# MotorPower.net
KiCad netlist of a schematic drawn in Altium Designer
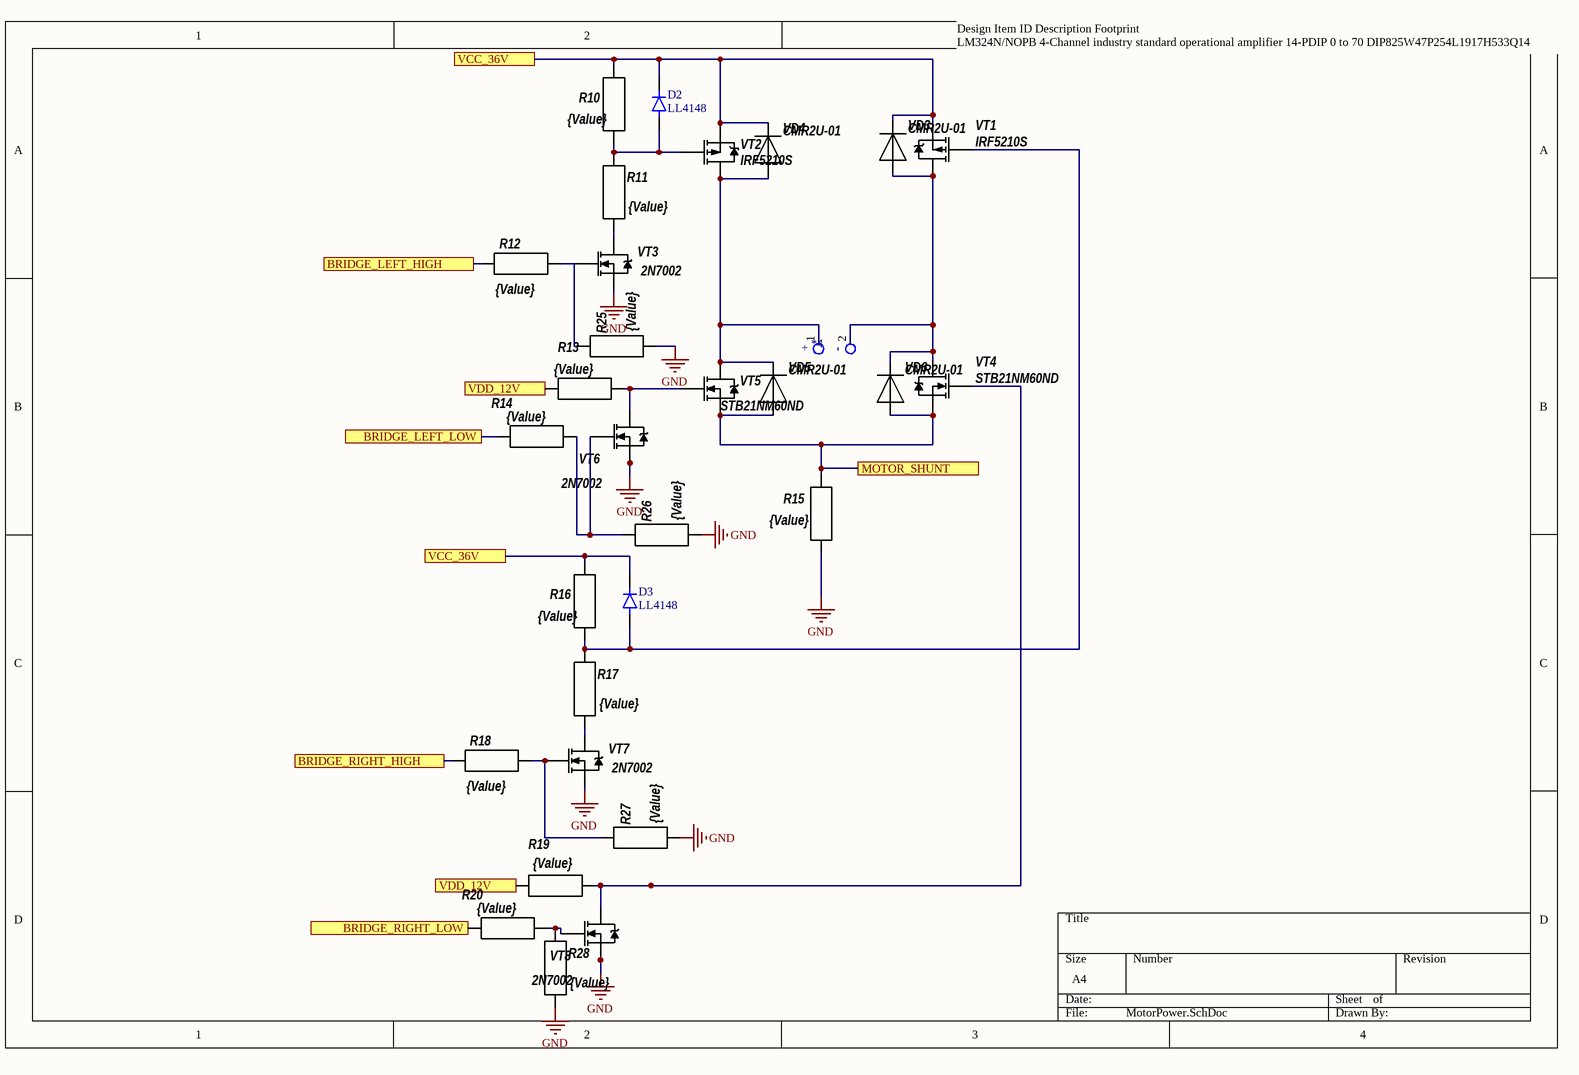
[diagram p0: MotorPower.SchDoc]

(export (version "E")
  (design (tool "Eeschema 10.0.6"))
  (components
    (comp (ref "*4")
      (value "Power connector 2pin")
      (footprint "Power connector 2 pin")
      (libsource (lib "Integrated_Library1") (part "Power connector 2pin"))
    )
    (comp (ref "D2")
      (value "LL4148")
      (footprint "DIO_LL4148")
      (description "Diode Standard 100V 200mA Surface Mount SOD-80")
      (fields (field (name "MF") "ON Semiconductor"))
      (libsource (lib "LL4148") (part "LL4148"))
    )
    (comp (ref "D3")
      (value "LL4148")
      (footprint "DIO_LL4148")
      (description "Diode Standard 100V 200mA Surface Mount SOD-80")
      (fields (field (name "MF") "ON Semiconductor"))
      (libsource (lib "LL4148") (part "LL4148"))
    )
    (comp (ref "R10")
      (value "{Value}")
      (footprint "R0805")
      (description "Резистор 0805")
      (fields (field (name "MANUFACTURER") "Yageo") (field (name "Comment") "Res 0805"))
      (libsource (lib "GIS_SMD components") (part "Res 0805"))
    )
    (comp (ref "R11")
      (value "{Value}")
      (footprint "R0805")
      (description "Резистор 0805")
      (fields (field (name "MANUFACTURER") "Yageo") (field (name "Comment") "Res 0805"))
      (libsource (lib "GIS_SMD components") (part "Res 0805"))
    )
    (comp (ref "R12")
      (value "{Value}")
      (footprint "R0805")
      (description "Резистор 0805")
      (fields (field (name "MANUFACTURER") "Yageo") (field (name "Comment") "Res 0805"))
      (libsource (lib "GIS_SMD components") (part "Res 0805"))
    )
    (comp (ref "R13")
      (value "{Value}")
      (footprint "R0805")
      (description "Резистор 0805")
      (fields (field (name "MANUFACTURER") "Yageo") (field (name "Comment") "Res 0805"))
      (libsource (lib "GIS_SMD components") (part "Res 0805"))
    )
    (comp (ref "R14")
      (value "{Value}")
      (footprint "R0805")
      (description "Резистор 0805")
      (fields (field (name "MANUFACTURER") "Yageo") (field (name "Comment") "Res 0805"))
      (libsource (lib "GIS_SMD components") (part "Res 0805"))
    )
    (comp (ref "R15")
      (value "{Value}")
      (footprint "R2512")
      (description "Резистор 2512")
      (fields (field (name "MANUFACTURER") "Yageo") (field (name "Comment") "Res 2512"))
      (libsource (lib "GIS_SMD components") (part "Res 2512"))
    )
    (comp (ref "R16")
      (value "{Value}")
      (footprint "R0805")
      (description "Резистор 0805")
      (fields (field (name "MANUFACTURER") "Yageo") (field (name "Comment") "Res 0805"))
      (libsource (lib "GIS_SMD components") (part "Res 0805"))
    )
    (comp (ref "R17")
      (value "{Value}")
      (footprint "R0805")
      (description "Резистор 0805")
      (fields (field (name "MANUFACTURER") "Yageo") (field (name "Comment") "Res 0805"))
      (libsource (lib "GIS_SMD components") (part "Res 0805"))
    )
    (comp (ref "R18")
      (value "{Value}")
      (footprint "R0805")
      (description "Резистор 0805")
      (fields (field (name "MANUFACTURER") "Yageo") (field (name "Comment") "Res 0805"))
      (libsource (lib "GIS_SMD components") (part "Res 0805"))
    )
    (comp (ref "R19")
      (value "{Value}")
      (footprint "R0805")
      (description "Резистор 0805")
      (fields (field (name "MANUFACTURER") "Yageo") (field (name "Comment") "Res 0805"))
      (libsource (lib "GIS_SMD components") (part "Res 0805"))
    )
    (comp (ref "R20")
      (value "{Value}")
      (footprint "R0805")
      (description "Резистор 0805")
      (fields (field (name "MANUFACTURER") "Yageo") (field (name "Comment") "Res 0805"))
      (libsource (lib "GIS_SMD components") (part "Res 0805"))
    )
    (comp (ref "R25")
      (value "{Value}")
      (footprint "R0805")
      (description "Резистор 0805")
      (fields (field (name "MANUFACTURER") "Yageo") (field (name "Comment") "Res 0805"))
      (libsource (lib "GIS_SMD components") (part "Res 0805"))
    )
    (comp (ref "R26")
      (value "{Value}")
      (footprint "R0805")
      (description "Резистор 0805")
      (fields (field (name "MANUFACTURER") "Yageo") (field (name "Comment") "Res 0805"))
      (libsource (lib "GIS_SMD components") (part "Res 0805"))
    )
    (comp (ref "R27")
      (value "{Value}")
      (footprint "R0805")
      (description "Резистор 0805")
      (fields (field (name "MANUFACTURER") "Yageo") (field (name "Comment") "Res 0805"))
      (libsource (lib "GIS_SMD components") (part "Res 0805"))
    )
    (comp (ref "R28")
      (value "{Value}")
      (footprint "R0805")
      (description "Резистор 0805")
      (fields (field (name "MANUFACTURER") "Yageo") (field (name "Comment") "Res 0805"))
      (libsource (lib "GIS_SMD components") (part "Res 0805"))
    )
    (comp (ref "VD3")
      (value "CMR2U-01")
      (footprint "SMB/DO-214AA")
      (description "Ultrafast, 100V, 2A, 50 ns")
      (fields (field (name "MANUFACTURER") "Central Semiconductor Corp"))
      (libsource (lib "GIS_Diods+Bridge") (part "CMR2U-01"))
    )
    (comp (ref "VD4")
      (value "CMR2U-01")
      (footprint "SMB/DO-214AA")
      (description "Ultrafast, 100V, 2A, 50 ns")
      (fields (field (name "MANUFACTURER") "Central Semiconductor Corp"))
      (libsource (lib "GIS_Diods+Bridge") (part "CMR2U-01"))
    )
    (comp (ref "VD5")
      (value "CMR2U-01")
      (footprint "SMB/DO-214AA")
      (description "Ultrafast, 100V, 2A, 50 ns")
      (fields (field (name "MANUFACTURER") "Central Semiconductor Corp"))
      (libsource (lib "GIS_Diods+Bridge") (part "CMR2U-01"))
    )
    (comp (ref "VD6")
      (value "CMR2U-01")
      (footprint "SMB/DO-214AA")
      (description "Ultrafast, 100V, 2A, 50 ns")
      (fields (field (name "MANUFACTURER") "Central Semiconductor Corp"))
      (libsource (lib "GIS_Diods+Bridge") (part "CMR2U-01"))
    )
    (comp (ref "VT1")
      (value "IRF5210S")
      (footprint "D2Pak")
      (description "P-chanel, 100V, 40A, 60 mOhm")
      (fields (field (name "MANUFACTURER") "International Rectifier"))
      (libsource (lib "GIS_transistor") (part "IRF5210S"))
    )
    (comp (ref "VT2")
      (value "IRF5210S")
      (footprint "D2Pak")
      (description "P-chanel, 100V, 40A, 60 mOhm")
      (fields (field (name "MANUFACTURER") "International Rectifier"))
      (libsource (lib "GIS_transistor") (part "IRF5210S"))
    )
    (comp (ref "VT3")
      (value "2N7002")
      (footprint "SOT-23")
      (description "60V, 200 mA, N-chanel")
      (fields (field (name "MANUFACTURER") "ON Semiconductor"))
      (libsource (lib "GIS_transistor") (part "2N7002"))
    )
    (comp (ref "VT4")
      (value "STB21NM60ND")
      (footprint "D2Pak")
      (description "D2pak, 600V, 17А, 170 mOhm")
      (fields (field (name "MANUFACTURER") "ST Microelectronics"))
      (libsource (lib "GIS_transistor") (part "STB21NM60ND"))
    )
    (comp (ref "VT5")
      (value "STB21NM60ND")
      (footprint "D2Pak")
      (description "D2pak, 600V, 17А, 170 mOhm")
      (fields (field (name "MANUFACTURER") "ST Microelectronics"))
      (libsource (lib "GIS_transistor") (part "STB21NM60ND"))
    )
    (comp (ref "VT6")
      (value "2N7002")
      (footprint "SOT-23")
      (description "60V, 200 mA, N-chanel")
      (fields (field (name "MANUFACTURER") "ON Semiconductor"))
      (libsource (lib "GIS_transistor") (part "2N7002"))
    )
    (comp (ref "VT7")
      (value "2N7002")
      (footprint "SOT-23")
      (description "60V, 200 mA, N-chanel")
      (fields (field (name "MANUFACTURER") "ON Semiconductor"))
      (libsource (lib "GIS_transistor") (part "2N7002"))
    )
    (comp (ref "VT8")
      (value "2N7002")
      (footprint "SOT-23")
      (description "60V, 200 mA, N-chanel")
      (fields (field (name "MANUFACTURER") "ON Semiconductor"))
      (libsource (lib "GIS_transistor") (part "2N7002"))
    )
  )
  (nets
    (net (code "1") (name "/BRIDGE_LEFT_HIGH") (class "Default")
      (node (ref "R12") (pin "2") (pinfunction "2_2") (pintype "passive"))
    )
    (net (code "2") (name "/BRIDGE_LEFT_LOW") (class "Default")
      (node (ref "R14") (pin "1") (pinfunction "1_1") (pintype "passive"))
    )
    (net (code "3") (name "/BRIDGE_RIGHT_HIGH") (class "Default")
      (node (ref "R18") (pin "2") (pinfunction "2_2") (pintype "passive"))
    )
    (net (code "4") (name "/BRIDGE_RIGHT_LOW") (class "Default")
      (node (ref "R20") (pin "1") (pinfunction "1_1") (pintype "passive"))
    )
    (net (code "5") (name "/MOTOR_SHUNT") (class "Default")
      (node (ref "R15") (pin "2") (pinfunction "2_2") (pintype "passive"))
      (node (ref "VD5") (pin "1") (pinfunction "1_1") (pintype "passive"))
      (node (ref "VD6") (pin "1") (pinfunction "1_1") (pintype "passive"))
      (node (ref "VT4") (pin "3") (pinfunction "S_3") (pintype "passive"))
      (node (ref "VT5") (pin "3") (pinfunction "S_3") (pintype "passive"))
    )
    (net (code "6") (name "/VCC_36V") (class "Default")
      (node (ref "D2") (pin "C") (pinfunction "C_C") (pintype "passive"))
      (node (ref "D3") (pin "C") (pinfunction "C_C") (pintype "passive"))
      (node (ref "R10") (pin "2") (pinfunction "2_2") (pintype "passive"))
      (node (ref "R16") (pin "2") (pinfunction "2_2") (pintype "passive"))
      (node (ref "VD3") (pin "2") (pinfunction "2_2") (pintype "passive"))
      (node (ref "VD4") (pin "2") (pinfunction "2_2") (pintype "passive"))
      (node (ref "VT1") (pin "3") (pinfunction "S_3") (pintype "passive"))
      (node (ref "VT2") (pin "3") (pinfunction "S_3") (pintype "passive"))
    )
    (net (code "7") (name "/VDD_12V") (class "Default")
      (node (ref "R13") (pin "1") (pinfunction "1_1") (pintype "passive"))
      (node (ref "R19") (pin "1") (pinfunction "1_1") (pintype "passive"))
    )
    (net (code "8") (name "GND") (class "Default")
      (node (ref "R15") (pin "1") (pinfunction "1_1") (pintype "passive"))
      (node (ref "R25") (pin "1") (pinfunction "1_1") (pintype "passive"))
      (node (ref "R26") (pin "1") (pinfunction "1_1") (pintype "passive"))
      (node (ref "R27") (pin "1") (pinfunction "1_1") (pintype "passive"))
      (node (ref "R28") (pin "1") (pinfunction "1_1") (pintype "passive"))
      (node (ref "VT3") (pin "2") (pinfunction "S_2") (pintype "passive"))
      (node (ref "VT6") (pin "2") (pinfunction "S_2") (pintype "passive"))
      (node (ref "VT7") (pin "2") (pinfunction "S_2") (pintype "passive"))
      (node (ref "VT8") (pin "2") (pinfunction "S_2") (pintype "passive"))
    )
    (net (code "9") (name "Net-(VT1-D)") (class "Default")
      (node (ref "*4") (pin "2") (pintype "passive"))
      (node (ref "VD3") (pin "1") (pinfunction "1_1") (pintype "passive"))
      (node (ref "VD6") (pin "2") (pinfunction "2_2") (pintype "passive"))
      (node (ref "VT1") (pin "2") (pinfunction "D_2") (pintype "passive"))
      (node (ref "VT4") (pin "2") (pinfunction "D_2") (pintype "passive"))
    )
    (net (code "10") (name "Net-(VT1-G)") (class "Default")
      (node (ref "D3") (pin "A") (pinfunction "A_A") (pintype "passive"))
      (node (ref "R16") (pin "1") (pinfunction "1_1") (pintype "passive"))
      (node (ref "R17") (pin "2") (pinfunction "2_2") (pintype "passive"))
      (node (ref "VT1") (pin "1") (pinfunction "G_1") (pintype "passive"))
    )
    (net (code "11") (name "Net-(VT2-D)") (class "Default")
      (node (ref "*4") (pin "1") (pintype "passive"))
      (node (ref "VD4") (pin "1") (pinfunction "1_1") (pintype "passive"))
      (node (ref "VD5") (pin "2") (pinfunction "2_2") (pintype "passive"))
      (node (ref "VT2") (pin "2") (pinfunction "D_2") (pintype "passive"))
      (node (ref "VT5") (pin "2") (pinfunction "D_2") (pintype "passive"))
    )
    (net (code "12") (name "Net-(VT2-G)") (class "Default")
      (node (ref "D2") (pin "A") (pinfunction "A_A") (pintype "passive"))
      (node (ref "R10") (pin "1") (pinfunction "1_1") (pintype "passive"))
      (node (ref "R11") (pin "2") (pinfunction "2_2") (pintype "passive"))
      (node (ref "VT2") (pin "1") (pinfunction "G_1") (pintype "passive"))
    )
    (net (code "13") (name "Net-(VT3-D)") (class "Default")
      (node (ref "R11") (pin "1") (pinfunction "1_1") (pintype "passive"))
      (node (ref "VT3") (pin "3") (pinfunction "D_3") (pintype "passive"))
    )
    (net (code "14") (name "Net-(VT3-G)") (class "Default")
      (node (ref "R12") (pin "1") (pinfunction "1_1") (pintype "passive"))
      (node (ref "R25") (pin "2") (pinfunction "2_2") (pintype "passive"))
      (node (ref "VT3") (pin "1") (pinfunction "G_1") (pintype "passive"))
    )
    (net (code "15") (name "Net-(VT4-G)") (class "Default")
      (node (ref "R19") (pin "2") (pinfunction "2_2") (pintype "passive"))
      (node (ref "VT4") (pin "1") (pinfunction "G_1") (pintype "passive"))
      (node (ref "VT8") (pin "3") (pinfunction "D_3") (pintype "passive"))
    )
    (net (code "16") (name "Net-(VT5-G)") (class "Default")
      (node (ref "R13") (pin "2") (pinfunction "2_2") (pintype "passive"))
      (node (ref "VT5") (pin "1") (pinfunction "G_1") (pintype "passive"))
      (node (ref "VT6") (pin "3") (pinfunction "D_3") (pintype "passive"))
    )
    (net (code "17") (name "Net-(VT6-G)") (class "Default")
      (node (ref "R14") (pin "2") (pinfunction "2_2") (pintype "passive"))
      (node (ref "R26") (pin "2") (pinfunction "2_2") (pintype "passive"))
      (node (ref "VT6") (pin "1") (pinfunction "G_1") (pintype "passive"))
    )
    (net (code "18") (name "Net-(VT7-D)") (class "Default")
      (node (ref "R17") (pin "1") (pinfunction "1_1") (pintype "passive"))
      (node (ref "VT7") (pin "3") (pinfunction "D_3") (pintype "passive"))
    )
    (net (code "19") (name "Net-(VT7-G)") (class "Default")
      (node (ref "R18") (pin "1") (pinfunction "1_1") (pintype "passive"))
      (node (ref "R27") (pin "2") (pinfunction "2_2") (pintype "passive"))
      (node (ref "VT7") (pin "1") (pinfunction "G_1") (pintype "passive"))
    )
    (net (code "20") (name "Net-(VT8-G)") (class "Default")
      (node (ref "R20") (pin "2") (pinfunction "2_2") (pintype "passive"))
      (node (ref "R28") (pin "2") (pinfunction "2_2") (pintype "passive"))
      (node (ref "VT8") (pin "1") (pinfunction "G_1") (pintype "passive"))
    )
  )
)
